# camera-tiny84-mark3.net
KiCad netlist of a schematic drawn in EAGLE
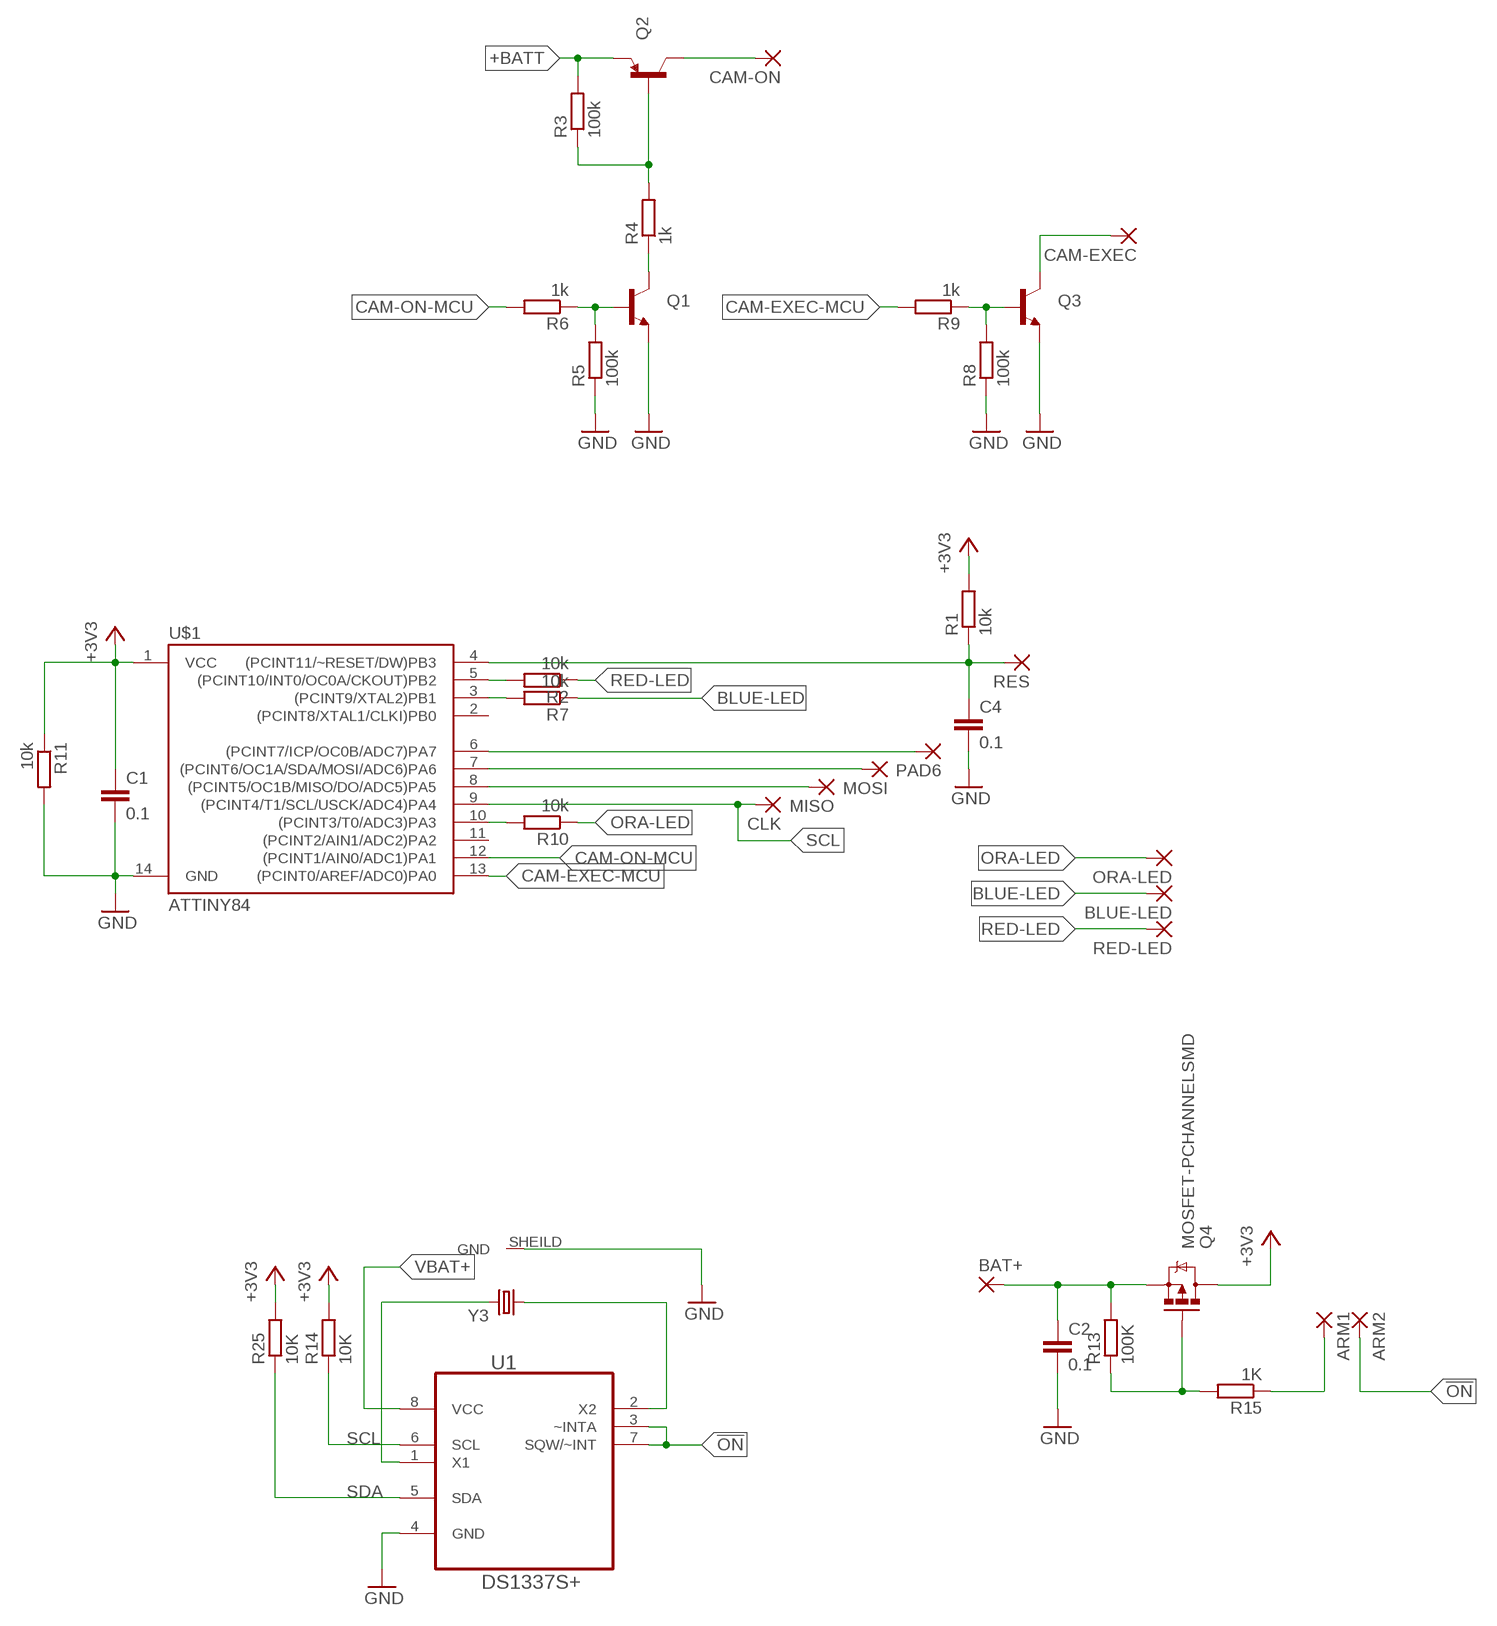
[diagram p0: schematic, sheet 1]

(export (version "E")
  (design (tool "Eeschema 10.0.6"))
  (components
    (comp (ref "ARM1")
      (value "SMD2")
      (footprint "eagle-import:SMD1,27-2,54")
      (libsource (lib "eagle-import") (part "SMD2"))
    )
    (comp (ref "ARM2")
      (value "SMD2")
      (footprint "eagle-import:SMD1,27-2,54")
      (libsource (lib "eagle-import") (part "SMD2"))
    )
    (comp (ref "BAT+")
      (value "SMD2")
      (footprint "eagle-import:SMD1,27-2,54")
      (libsource (lib "eagle-import") (part "SMD2"))
    )
    (comp (ref "BLUE-LED")
      (value "SMD2")
      (footprint "eagle-import:SMD1,27-2,54")
      (libsource (lib "eagle-import") (part "SMD2"))
    )
    (comp (ref "C1")
      (value "0.1")
      (footprint "eagle-import:C0603")
      (libsource (lib "eagle-import") (part "C-EUC0603"))
    )
    (comp (ref "C2")
      (value "0.1")
      (footprint "eagle-import:C0603")
      (libsource (lib "eagle-import") (part "C-EUC0603"))
    )
    (comp (ref "C4")
      (value "0.1")
      (footprint "eagle-import:C1206")
      (libsource (lib "eagle-import") (part "C-EUC1206"))
    )
    (comp (ref "CAM-EXEC")
      (value "SMD2")
      (footprint "eagle-import:SMD1,27-2,54")
      (libsource (lib "eagle-import") (part "SMD2"))
    )
    (comp (ref "CAM-ON")
      (value "SMD2")
      (footprint "eagle-import:SMD1,27-2,54")
      (libsource (lib "eagle-import") (part "SMD2"))
    )
    (comp (ref "CLK")
      (value "1,6/0,8")
      (footprint "eagle-import:1,6_0,8")
      (libsource (lib "eagle-import") (part "1,6/0,8"))
    )
    (comp (ref "MISO")
      (value "1,6/0,8")
      (footprint "eagle-import:1,6_0,8")
      (libsource (lib "eagle-import") (part "1,6/0,8"))
    )
    (comp (ref "MOSI")
      (value "1,6/0,8")
      (footprint "eagle-import:1,6_0,8")
      (libsource (lib "eagle-import") (part "1,6/0,8"))
    )
    (comp (ref "ORA-LED")
      (value "SMD2")
      (footprint "eagle-import:SMD1,27-2,54")
      (libsource (lib "eagle-import") (part "SMD2"))
    )
    (comp (ref "PAD6")
      (value "SMD2")
      (footprint "eagle-import:SMD1,27-2,54")
      (libsource (lib "eagle-import") (part "SMD2"))
    )
    (comp (ref "Q1")
      (value "TRANSISTOR_NPNSOT23-3")
      (footprint "eagle-import:SOT23-3")
      (libsource (lib "eagle-import") (part "TRANSISTOR_NPNSOT23-3"))
    )
    (comp (ref "Q2")
      (value "TRANSISTOR_PNPSMD")
      (footprint "eagle-import:SOT23-3")
      (libsource (lib "eagle-import") (part "TRANSISTOR_PNPSMD"))
    )
    (comp (ref "Q3")
      (value "TRANSISTOR_NPNSOT23-3")
      (footprint "eagle-import:SOT23-3")
      (libsource (lib "eagle-import") (part "TRANSISTOR_NPNSOT23-3"))
    )
    (comp (ref "Q4")
      (value "MOSFET-PCHANNELSMD")
      (footprint "eagle-import:SOT23-3")
      (libsource (lib "eagle-import") (part "MOSFET-PCHANNELSMD"))
    )
    (comp (ref "R1")
      (value "10k")
      (footprint "eagle-import:R0603")
      (libsource (lib "eagle-import") (part "R-EU_R0603"))
    )
    (comp (ref "R2")
      (value "10k")
      (footprint "eagle-import:R0603")
      (libsource (lib "eagle-import") (part "R-EU_R0603"))
    )
    (comp (ref "R3")
      (value "100k")
      (footprint "eagle-import:R0603")
      (libsource (lib "eagle-import") (part "R-EU_R0603"))
    )
    (comp (ref "R4")
      (value "1k")
      (footprint "eagle-import:R0603")
      (libsource (lib "eagle-import") (part "R-EU_R0603"))
    )
    (comp (ref "R5")
      (value "100k")
      (footprint "eagle-import:R0603")
      (libsource (lib "eagle-import") (part "R-EU_R0603"))
    )
    (comp (ref "R6")
      (value "1k")
      (footprint "eagle-import:R0603")
      (libsource (lib "eagle-import") (part "R-EU_R0603"))
    )
    (comp (ref "R7")
      (value "10k")
      (footprint "eagle-import:R0603")
      (libsource (lib "eagle-import") (part "R-EU_R0603"))
    )
    (comp (ref "R8")
      (value "100k")
      (footprint "eagle-import:R0603")
      (libsource (lib "eagle-import") (part "R-EU_R0603"))
    )
    (comp (ref "R9")
      (value "1k")
      (footprint "eagle-import:R0603")
      (libsource (lib "eagle-import") (part "R-EU_R0603"))
    )
    (comp (ref "R10")
      (value "10k")
      (footprint "eagle-import:R0603")
      (libsource (lib "eagle-import") (part "R-EU_R0603"))
    )
    (comp (ref "R11")
      (value "10k")
      (footprint "eagle-import:R0603")
      (libsource (lib "eagle-import") (part "R-EU_R0603"))
    )
    (comp (ref "R13")
      (value "100K")
      (footprint "eagle-import:R0603")
      (libsource (lib "eagle-import") (part "resistor_R-EU_R0603"))
    )
    (comp (ref "R14")
      (value "10K")
      (footprint "eagle-import:R0603")
      (libsource (lib "eagle-import") (part "resistor_R-EU_R0603"))
    )
    (comp (ref "R15")
      (value "1K")
      (footprint "eagle-import:R0603")
      (libsource (lib "eagle-import") (part "resistor_R-EU_R0603"))
    )
    (comp (ref "R25")
      (value "10K")
      (footprint "eagle-import:R0603")
      (libsource (lib "eagle-import") (part "resistor_R-EU_R0603"))
    )
    (comp (ref "RED-LED")
      (value "SMD2")
      (footprint "eagle-import:SMD1,27-2,54")
      (libsource (lib "eagle-import") (part "SMD2"))
    )
    (comp (ref "RES")
      (value "1,6/0,8")
      (footprint "eagle-import:1,6_0,8")
      (libsource (lib "eagle-import") (part "1,6/0,8"))
    )
    (comp (ref "U$1")
      (value "ATTINY84")
      (footprint "eagle-import:SO14")
      (libsource (lib "eagle-import") (part "ATTINY84"))
    )
    (comp (ref "U1")
      (value "DS1337S+")
      (footprint "eagle-import:SOIC127P600X175-8N")
      (libsource (lib "eagle-import") (part "DS1337S+"))
    )
    (comp (ref "Y3")
      (value "CRYSTAL32-SMD_CRYSTAL32-SMD")
      (footprint "eagle-import:CRYSTAL32-SMD_CRYSTAL-32KHZ-SMD")
      (libsource (lib "eagle-import") (part "CRYSTAL32-SMD_CRYSTAL32-SMD"))
    )
  )
  (nets
    (net (code "1") (name "+3V3") (class "Default")
      (node (ref "C1") (pin "1") (pinfunction "1_1") (pintype "passive"))
      (node (ref "Q4") (pin "3") (pinfunction "D_3") (pintype "passive"))
      (node (ref "R1") (pin "2") (pinfunction "2_2") (pintype "passive"))
      (node (ref "R11") (pin "1") (pinfunction "1_1") (pintype "passive"))
      (node (ref "R14") (pin "2") (pinfunction "2_2") (pintype "passive"))
      (node (ref "R25") (pin "2") (pinfunction "2_2") (pintype "passive"))
      (node (ref "U$1") (pin "1") (pinfunction "VCC_1") (pintype "bidirectional"))
    )
    (net (code "2") (name "+BATT") (class "Default")
      (node (ref "Q2") (pin "2") (pinfunction "E_2") (pintype "passive"))
      (node (ref "R3") (pin "2") (pinfunction "2_2") (pintype "passive"))
    )
    (net (code "3") (name "/SDA") (class "Default")
      (node (ref "MOSI") (pin "1") (pinfunction "P_1") (pintype "passive"))
      (node (ref "R25") (pin "1") (pinfunction "1_1") (pintype "passive"))
      (node (ref "U$1") (pin "7") (pinfunction "(PCINT6/OC1A/SDA/MOSI/ADC6)PA6_7") (pintype "bidirectional"))
      (node (ref "U1") (pin "5") (pinfunction "SDA_5") (pintype "bidirectional"))
    )
    (net (code "4") (name "/~{ON}") (class "Default")
      (node (ref "ARM2") (pin "1") (pinfunction "P_1") (pintype "passive"))
      (node (ref "U1") (pin "3") (pinfunction "~{INTA}_3") (pintype "output"))
      (node (ref "U1") (pin "7") (pinfunction "SQW/~{INT}_7") (pintype "output"))
    )
    (net (code "5") (name "BLUE-LED") (class "Default")
      (node (ref "BLUE-LED") (pin "1") (pinfunction "P_1") (pintype "passive"))
      (node (ref "R7") (pin "1") (pinfunction "1_1") (pintype "passive"))
    )
    (net (code "6") (name "CAM-EXEC-MCU") (class "Default")
      (node (ref "R9") (pin "2") (pinfunction "2_2") (pintype "passive"))
      (node (ref "U$1") (pin "13") (pinfunction "(PCINT0/AREF/ADC0)PA0_13") (pintype "bidirectional"))
    )
    (net (code "7") (name "CAM-ON-MCU") (class "Default")
      (node (ref "R6") (pin "2") (pinfunction "2_2") (pintype "passive"))
      (node (ref "U$1") (pin "12") (pinfunction "(PCINT1/AIN0/ADC1)PA1_12") (pintype "bidirectional"))
    )
    (net (code "8") (name "GND") (class "Default")
      (node (ref "C1") (pin "2") (pinfunction "2_2") (pintype "passive"))
      (node (ref "C2") (pin "2") (pinfunction "2_2") (pintype "passive"))
      (node (ref "C4") (pin "2") (pinfunction "2_2") (pintype "passive"))
      (node (ref "Q1") (pin "2") (pinfunction "E_2") (pintype "passive"))
      (node (ref "Q3") (pin "2") (pinfunction "E_2") (pintype "passive"))
      (node (ref "R11") (pin "2") (pinfunction "2_2") (pintype "passive"))
      (node (ref "R5") (pin "1") (pinfunction "1_1") (pintype "passive"))
      (node (ref "R8") (pin "1") (pinfunction "1_1") (pintype "passive"))
      (node (ref "U$1") (pin "14") (pinfunction "GND_14") (pintype "bidirectional"))
      (node (ref "U1") (pin "4") (pinfunction "GND_4") (pintype "passive"))
      (node (ref "Y3") (pin "SHEILD") (pinfunction "GND_SHEILD") (pintype "bidirectional"))
    )
    (net (code "9") (name "Net-(ARM1-P)") (class "Default")
      (node (ref "ARM1") (pin "1") (pinfunction "P_1") (pintype "passive"))
      (node (ref "R15") (pin "1") (pinfunction "1_1") (pintype "passive"))
    )
    (net (code "10") (name "Net-(CAM-EXEC-P)") (class "Default")
      (node (ref "CAM-EXEC") (pin "1") (pinfunction "P_1") (pintype "passive"))
      (node (ref "Q3") (pin "3") (pinfunction "C_3") (pintype "passive"))
    )
    (net (code "11") (name "Net-(CAM-ON-P)") (class "Default")
      (node (ref "CAM-ON") (pin "1") (pinfunction "P_1") (pintype "passive"))
      (node (ref "Q2") (pin "3") (pinfunction "C_3") (pintype "passive"))
    )
    (net (code "12") (name "Net-(MISO-P)") (class "Default")
      (node (ref "MISO") (pin "1") (pinfunction "P_1") (pintype "passive"))
      (node (ref "U$1") (pin "8") (pinfunction "(PCINT5/OC1B/MISO/DO/ADC5)PA5_8") (pintype "bidirectional"))
    )
    (net (code "13") (name "Net-(PAD6-P)") (class "Default")
      (node (ref "PAD6") (pin "1") (pinfunction "P_1") (pintype "passive"))
      (node (ref "U$1") (pin "6") (pinfunction "(PCINT7/ICP/OC0B/ADC7)PA7_6") (pintype "bidirectional"))
    )
    (net (code "14") (name "Net-(Q1-B)") (class "Default")
      (node (ref "Q1") (pin "1") (pinfunction "B_1") (pintype "passive"))
      (node (ref "R5") (pin "2") (pinfunction "2_2") (pintype "passive"))
      (node (ref "R6") (pin "1") (pinfunction "1_1") (pintype "passive"))
    )
    (net (code "15") (name "Net-(Q1-C)") (class "Default")
      (node (ref "Q1") (pin "3") (pinfunction "C_3") (pintype "passive"))
      (node (ref "R4") (pin "1") (pinfunction "1_1") (pintype "passive"))
    )
    (net (code "16") (name "Net-(Q2-B)") (class "Default")
      (node (ref "Q2") (pin "1") (pinfunction "B_1") (pintype "passive"))
      (node (ref "R3") (pin "1") (pinfunction "1_1") (pintype "passive"))
      (node (ref "R4") (pin "2") (pinfunction "2_2") (pintype "passive"))
    )
    (net (code "17") (name "Net-(Q3-B)") (class "Default")
      (node (ref "Q3") (pin "1") (pinfunction "B_1") (pintype "passive"))
      (node (ref "R8") (pin "2") (pinfunction "2_2") (pintype "passive"))
      (node (ref "R9") (pin "1") (pinfunction "1_1") (pintype "passive"))
    )
    (net (code "18") (name "Net-(Q4-G)") (class "Default")
      (node (ref "Q4") (pin "1") (pinfunction "G_1") (pintype "passive"))
      (node (ref "R13") (pin "1") (pinfunction "1_1") (pintype "passive"))
      (node (ref "R15") (pin "2") (pinfunction "2_2") (pintype "passive"))
    )
    (net (code "19") (name "Net-(RES-P)") (class "Default")
      (node (ref "C4") (pin "1") (pinfunction "1_1") (pintype "passive"))
      (node (ref "R1") (pin "1") (pinfunction "1_1") (pintype "passive"))
      (node (ref "RES") (pin "1") (pinfunction "P_1") (pintype "passive"))
      (node (ref "U$1") (pin "4") (pinfunction "(PCINT11/~{RESET/DW})PB3_4") (pintype "bidirectional"))
    )
    (net (code "20") (name "Net-(U$1-(PCINT3{slash}T0{slash}ADC3)PA3)") (class "Default")
      (node (ref "R10") (pin "2") (pinfunction "2_2") (pintype "passive"))
      (node (ref "U$1") (pin "10") (pinfunction "(PCINT3/T0/ADC3)PA3_10") (pintype "bidirectional"))
    )
    (net (code "21") (name "Net-(U$1-(PCINT9{slash}XTAL2)PB1)") (class "Default")
      (node (ref "R7") (pin "2") (pinfunction "2_2") (pintype "passive"))
      (node (ref "U$1") (pin "3") (pinfunction "(PCINT9/XTAL2)PB1_3") (pintype "bidirectional"))
    )
    (net (code "22") (name "Net-(U$1-(PCINT10{slash}INT0{slash}OC0A{slash}CKOUT)PB2)") (class "Default")
      (node (ref "R2") (pin "2") (pinfunction "2_2") (pintype "passive"))
      (node (ref "U$1") (pin "5") (pinfunction "(PCINT10/INT0/OC0A/CKOUT)PB2_5") (pintype "bidirectional"))
    )
    (net (code "23") (name "Net-(U1-X1)") (class "Default")
      (node (ref "U1") (pin "1") (pinfunction "X1_1") (pintype "input"))
      (node (ref "Y3") (pin "X2") (pinfunction "2_X2") (pintype "passive"))
    )
    (net (code "24") (name "Net-(U1-X2)") (class "Default")
      (node (ref "U1") (pin "2") (pinfunction "X2_2") (pintype "passive"))
      (node (ref "Y3") (pin "X1") (pinfunction "1_X1") (pintype "passive"))
    )
    (net (code "25") (name "ORA-LED") (class "Default")
      (node (ref "ORA-LED") (pin "1") (pinfunction "P_1") (pintype "passive"))
      (node (ref "R10") (pin "1") (pinfunction "1_1") (pintype "passive"))
    )
    (net (code "26") (name "RED-LED") (class "Default")
      (node (ref "R2") (pin "1") (pinfunction "1_1") (pintype "passive"))
      (node (ref "RED-LED") (pin "1") (pinfunction "P_1") (pintype "passive"))
    )
    (net (code "27") (name "SCL") (class "Default")
      (node (ref "CLK") (pin "1") (pinfunction "P_1") (pintype "passive"))
      (node (ref "R14") (pin "1") (pinfunction "1_1") (pintype "passive"))
      (node (ref "U$1") (pin "9") (pinfunction "(PCINT4/T1/SCL/USCK/ADC4)PA4_9") (pintype "bidirectional"))
      (node (ref "U1") (pin "6") (pinfunction "SCL_6") (pintype "input"))
    )
    (net (code "28") (name "VBAT+") (class "Default")
      (node (ref "BAT+") (pin "1") (pinfunction "P_1") (pintype "passive"))
      (node (ref "C2") (pin "1") (pinfunction "1_1") (pintype "passive"))
      (node (ref "Q4") (pin "2") (pinfunction "S_2") (pintype "passive"))
      (node (ref "R13") (pin "2") (pinfunction "2_2") (pintype "passive"))
      (node (ref "U1") (pin "8") (pinfunction "VCC_8") (pintype "power_in"))
    )
    (net (code "29") (name "unconnected-(U$1-(PCINT2{slash}AIN1{slash}ADC2)PA2-Pad11)") (class "Default")
      (node (ref "U$1") (pin "11") (pinfunction "(PCINT2/AIN1/ADC2)PA2_11") (pintype "bidirectional"))
    )
    (net (code "30") (name "unconnected-(U$1-(PCINT8{slash}XTAL1{slash}CLKI)PB0-Pad2)") (class "Default")
      (node (ref "U$1") (pin "2") (pinfunction "(PCINT8/XTAL1/CLKI)PB0_2") (pintype "bidirectional"))
    )
  )
)
